# Sheet1.net
KiCad netlist of a schematic drawn in Altium Designer
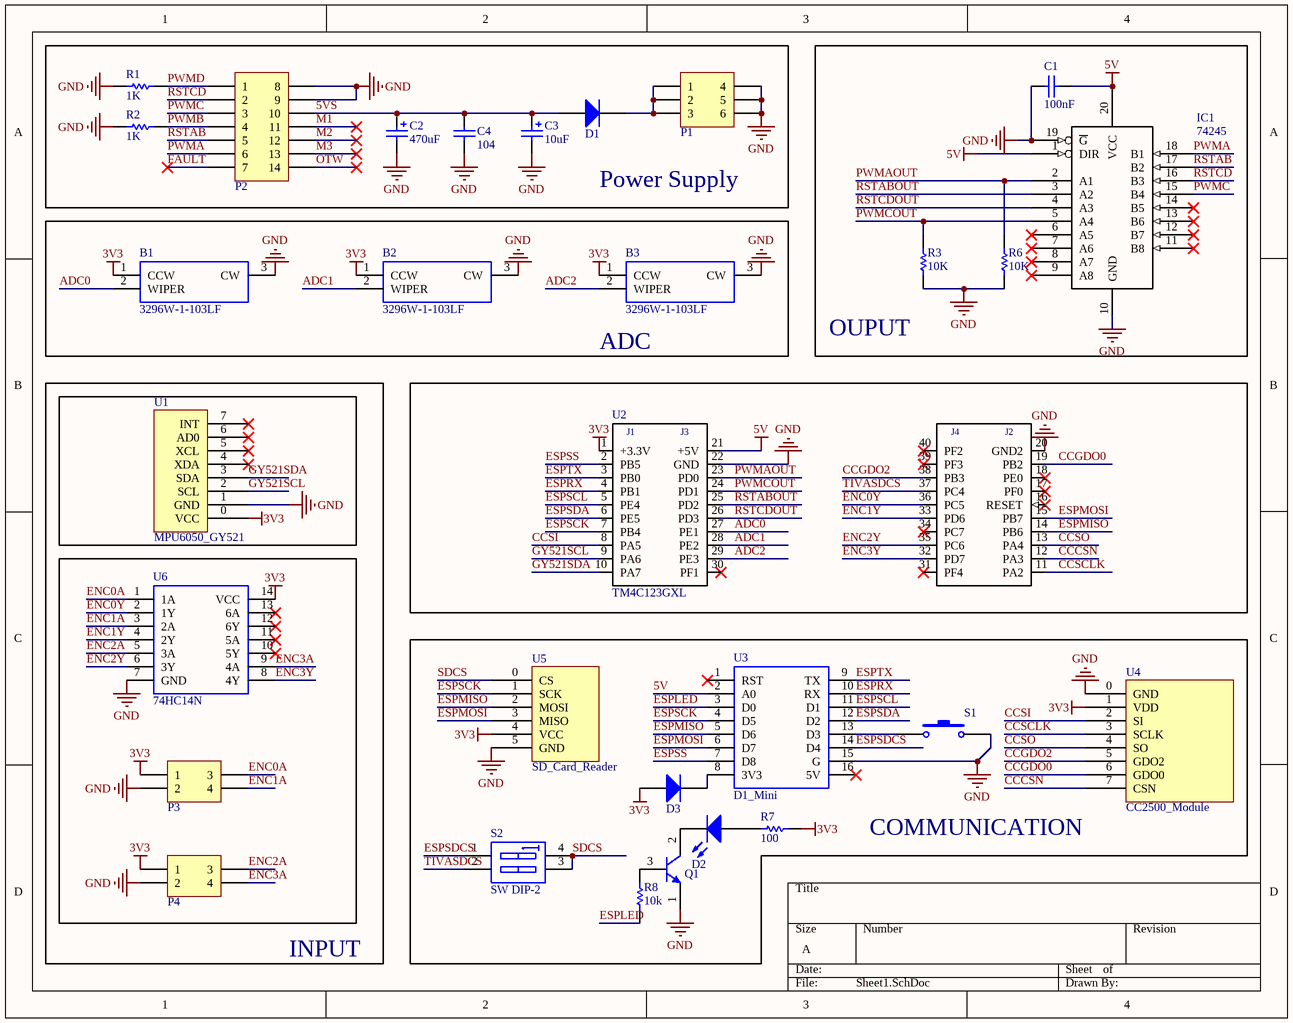
[diagram p0: Sheet1.SchDoc]

(export (version "E")
  (design (tool "Eeschema 10.0.6"))
  (components
    (comp (ref "B1")
      (value "3296W-1-103LF")
      (footprint "Rheostat")
      (fields (field (name "RS PART NUMBER") "5219647P"))
      (libsource (lib "AltiumLib") (part "Rheostat"))
    )
    (comp (ref "B2")
      (value "3296W-1-103LF")
      (footprint "Rheostat")
      (fields (field (name "RS PART NUMBER") "5219647P"))
      (libsource (lib "AltiumLib") (part "Rheostat"))
    )
    (comp (ref "B3")
      (value "3296W-1-103LF")
      (footprint "Rheostat")
      (fields (field (name "RS PART NUMBER") "5219647P"))
      (libsource (lib "AltiumLib") (part "Rheostat"))
    )
    (comp (ref "C1")
      (value "100nF")
      (footprint "CN1")
      (description "Capacitor")
      (fields (field (name "Comment") "Cap Non-Pol"))
      (libsource (lib "PIF_Library") (part "Cap Non-Pol"))
    )
    (comp (ref "C2")
      (value "470uF")
      (footprint "CP1/2")
      (description "Polarized Capacitor (Radial)")
      (fields (field (name "Comment") "Cap Pol"))
      (libsource (lib "PIF_Library") (part "Cap Pol"))
    )
    (comp (ref "C3")
      (value "10uF")
      (footprint "CP1/2")
      (description "Polarized Capacitor (Radial)")
      (fields (field (name "Comment") "Cap Pol"))
      (libsource (lib "PIF_Library") (part "Cap Pol"))
    )
    (comp (ref "C4")
      (value "104")
      (footprint "CN1")
      (description "Capacitor")
      (fields (field (name "Comment") "Cap Non-Pol"))
      (libsource (lib "PIF_Library") (part "Cap Non-Pol"))
    )
    (comp (ref "D1")
      (value "Diode")
      (footprint "D1A")
      (description "Default Diode")
      (libsource (lib "PIF_Library") (part "Diode"))
    )
    (comp (ref "D2") (value "LED") (footprint "LED-3mm") (libsource (lib "PIF_Library") (part "LED")))
    (comp (ref "D3")
      (value "Diode")
      (footprint "D1A")
      (description "Default Diode")
      (libsource (lib "PIF_Library") (part "Diode"))
    )
    (comp (ref "IC1")
      (value "74245")
      (footprint "DIP20")
      (description "Octal bus tranceiver; 3-state")
      (fields (field (name "COPYRIGHT BY") "VanDungEvn@gmail.com"))
      (libsource (lib "My Library") (part "74245_1"))
    )
    (comp (ref "P1")
      (value "Header 3X2")
      (footprint "JP3x2")
      (description "Header, 3-Pin, Dual row")
      (fields (field (name "PUBLISHER") "Altium Limited"))
      (libsource (lib "PIF_Library") (part "Header 3X2"))
    )
    (comp (ref "P2")
      (value "Header 7X2")
      (footprint "JP7X2")
      (description "Header, 7-Pin, Dual row")
      (fields (field (name "PUBLISHER") "Altium Limited"))
      (libsource (lib "PIF_Library") (part "Header 7X2"))
    )
    (comp (ref "P3")
      (value "Header 2X2")
      (footprint "JP2X2")
      (description "Header, 2-Pin, Dual row")
      (fields (field (name "PUBLISHER") "Altium Limited"))
      (libsource (lib "PIF_Library") (part "Header 2X2"))
    )
    (comp (ref "P4")
      (value "Header 2X2")
      (footprint "JP2X2")
      (description "Header, 2-Pin, Dual row")
      (fields (field (name "PUBLISHER") "Altium Limited"))
      (libsource (lib "PIF_Library") (part "Header 2X2"))
    )
    (comp (ref "Q1")
      (value "C1815")
      (footprint "QTO-92")
      (description "NPN Bipolar Transistor")
      (libsource (lib "PIF_Library") (part "C1815"))
    )
    (comp (ref "R1")
      (value "1K")
      (footprint "RES 1/2W")
      (description "Resistor")
      (fields (field (name "Comment") "RESISTOR"))
      (libsource (lib "PIF_Library") (part "RESISTOR"))
    )
    (comp (ref "R2")
      (value "1K")
      (footprint "RES 1/2W")
      (description "Resistor")
      (fields (field (name "Comment") "RESISTOR"))
      (libsource (lib "PIF_Library") (part "RESISTOR"))
    )
    (comp (ref "R3")
      (value "10K")
      (footprint "RES 1/2W")
      (description "Resistor")
      (fields (field (name "Comment") "RESISTOR"))
      (libsource (lib "PIF_Library") (part "RESISTOR"))
    )
    (comp (ref "R6")
      (value "10K")
      (footprint "RES 1/2W")
      (description "Resistor")
      (fields (field (name "Comment") "RESISTOR"))
      (libsource (lib "PIF_Library") (part "RESISTOR"))
    )
    (comp (ref "R7")
      (value "100")
      (footprint "RES 1/2W")
      (description "Resistor")
      (fields (field (name "Comment") "RESISTOR"))
      (libsource (lib "PIF_Library") (part "RESISTOR"))
    )
    (comp (ref "R8")
      (value "10k")
      (footprint "RES 1/2W")
      (description "Resistor")
      (fields (field (name "Comment") "RESISTOR"))
      (libsource (lib "PIF_Library") (part "RESISTOR"))
    )
    (comp (ref "S1")
      (value "Tact SW - 2Pin")
      (footprint "SW2")
      (description "Switch button 2 pin")
      (libsource (lib "PIF_Library") (part "Tact SW - 2Pin"))
    )
    (comp (ref "S2")
      (value "SW DIP-2")
      (footprint "DIPSWITCH2")
      (description "DIP Switch, 2 Position, SPST")
      (fields (field (name "PUBLISHER") "Altium Limited"))
      (libsource (lib "My Library") (part "SW DIP-2"))
    )
    (comp (ref "U1")
      (value "MPU6050_GY521")
      (footprint "MPU6050_GY521")
      (libsource (lib "AltiumLib") (part "MPU6050_GY521"))
    )
    (comp (ref "U2")
      (value "TM4C123GXL")
      (footprint "EK-TM4C123GXL")
      (libsource (lib "AltiumLib") (part "EK-TM4C123GXL"))
    )
    (comp (ref "U3") (value "D1_Mini") (footprint "D1_Mini") (libsource (lib "AltiumLib") (part "D1_Mini")))
    (comp (ref "U4")
      (value "CC2500_Module")
      (footprint "CC2500_module")
      (libsource (lib "AltiumLib") (part "CC2500_Module"))
    )
    (comp (ref "U5")
      (value "SD_Card_Reader")
      (footprint "SD_Card_Reader")
      (libsource (lib "AltiumLib") (part "SD_Card_Reader"))
    )
    (comp (ref "U6") (value "74HC14N") (footprint "74HC14N") (libsource (lib "AltiumLib") (part "74HC14N")))
  )
  (nets
    (net (code "1") (name "/5VS") (class "Default")
      (node (ref "C2") (pin "1") (pinfunction "1_1") (pintype "passive"))
      (node (ref "C3") (pin "1") (pinfunction "1_1") (pintype "passive"))
      (node (ref "C4") (pin "1") (pinfunction "1_1") (pintype "passive"))
      (node (ref "D1") (pin "1") (pinfunction "A_1") (pintype "passive"))
      (node (ref "P2") (pin "10") (pinfunction "10_10") (pintype "passive"))
    )
    (net (code "2") (name "/ADC0") (class "Default")
      (node (ref "B1") (pin "2") (pinfunction "WIPER_2") (pintype "passive"))
      (node (ref "U2") (pin "27") (pinfunction "PE1_27") (pintype "bidirectional"))
    )
    (net (code "3") (name "/ADC1") (class "Default")
      (node (ref "B2") (pin "2") (pinfunction "WIPER_2") (pintype "passive"))
      (node (ref "U2") (pin "28") (pinfunction "PE2_28") (pintype "bidirectional"))
    )
    (net (code "4") (name "/ADC2") (class "Default")
      (node (ref "B3") (pin "2") (pinfunction "WIPER_2") (pintype "passive"))
      (node (ref "U2") (pin "29") (pinfunction "PE3_29") (pintype "bidirectional"))
    )
    (net (code "5") (name "/CCCSN") (class "Default")
      (node (ref "U2") (pin "12") (pinfunction "PA3_12") (pintype "bidirectional"))
      (node (ref "U4") (pin "7") (pinfunction "CSN_7") (pintype "passive"))
    )
    (net (code "6") (name "/CCGDO0") (class "Default")
      (node (ref "U2") (pin "19") (pinfunction "PB2_19") (pintype "bidirectional"))
      (node (ref "U4") (pin "6") (pinfunction "GDO0_6") (pintype "passive"))
    )
    (net (code "7") (name "/CCGDO2") (class "Default")
      (node (ref "U2") (pin "38") (pinfunction "PB3_38") (pintype "bidirectional"))
      (node (ref "U4") (pin "5") (pinfunction "GDO2_5") (pintype "passive"))
    )
    (net (code "8") (name "/CCSCLK") (class "Default")
      (node (ref "U2") (pin "11") (pinfunction "PA2_11") (pintype "bidirectional"))
      (node (ref "U4") (pin "3") (pinfunction "SCLK_3") (pintype "passive"))
    )
    (net (code "9") (name "/CCSI") (class "Default")
      (node (ref "U2") (pin "8") (pinfunction "PA5_8") (pintype "bidirectional"))
      (node (ref "U4") (pin "2") (pinfunction "SI_2") (pintype "passive"))
    )
    (net (code "10") (name "/CCSO") (class "Default")
      (node (ref "U2") (pin "13") (pinfunction "PA4_13") (pintype "bidirectional"))
      (node (ref "U4") (pin "4") (pinfunction "SO_4") (pintype "passive"))
    )
    (net (code "11") (name "/ENC0A") (class "Default")
      (node (ref "P3") (pin "3") (pinfunction "3_3") (pintype "passive"))
      (node (ref "U6") (pin "1") (pinfunction "1A_1") (pintype "passive"))
    )
    (net (code "12") (name "/ENC0Y") (class "Default")
      (node (ref "U2") (pin "36") (pinfunction "PC5_36") (pintype "bidirectional"))
      (node (ref "U6") (pin "2") (pinfunction "1Y_2") (pintype "passive"))
    )
    (net (code "13") (name "/ENC1A") (class "Default")
      (node (ref "P3") (pin "4") (pinfunction "4_4") (pintype "passive"))
      (node (ref "U6") (pin "3") (pinfunction "2A_3") (pintype "passive"))
    )
    (net (code "14") (name "/ENC1Y") (class "Default")
      (node (ref "U2") (pin "33") (pinfunction "PD6_33") (pintype "bidirectional"))
      (node (ref "U6") (pin "4") (pinfunction "2Y_4") (pintype "passive"))
    )
    (net (code "15") (name "/ENC2A") (class "Default")
      (node (ref "P4") (pin "3") (pinfunction "3_3") (pintype "passive"))
      (node (ref "U6") (pin "5") (pinfunction "3A_5") (pintype "passive"))
    )
    (net (code "16") (name "/ENC2Y") (class "Default")
      (node (ref "U2") (pin "35") (pinfunction "PC6_35") (pintype "bidirectional"))
      (node (ref "U6") (pin "6") (pinfunction "3Y_6") (pintype "passive"))
    )
    (net (code "17") (name "/ENC3A") (class "Default")
      (node (ref "P4") (pin "4") (pinfunction "4_4") (pintype "passive"))
      (node (ref "U6") (pin "9") (pinfunction "4A_9") (pintype "passive"))
    )
    (net (code "18") (name "/ENC3Y") (class "Default")
      (node (ref "U2") (pin "32") (pinfunction "PD7_32") (pintype "bidirectional"))
      (node (ref "U6") (pin "8") (pinfunction "4Y_8") (pintype "passive"))
    )
    (net (code "19") (name "/ESPLED") (class "Default")
      (node (ref "R8") (pin "1") (pinfunction "1_1") (pintype "passive"))
      (node (ref "U3") (pin "3") (pinfunction "D0_3") (pintype "passive"))
    )
    (net (code "20") (name "/ESPMISO") (class "Default")
      (node (ref "U2") (pin "14") (pinfunction "PB6_14") (pintype "bidirectional"))
      (node (ref "U3") (pin "5") (pinfunction "D6_5") (pintype "passive"))
      (node (ref "U5") (pin "2") (pinfunction "MOSI_2") (pintype "passive"))
    )
    (net (code "21") (name "/ESPMOSI") (class "Default")
      (node (ref "U2") (pin "15") (pinfunction "PB7_15") (pintype "bidirectional"))
      (node (ref "U3") (pin "6") (pinfunction "D7_6") (pintype "passive"))
      (node (ref "U5") (pin "3") (pinfunction "MISO_3") (pintype "passive"))
    )
    (net (code "22") (name "/ESPRX") (class "Default")
      (node (ref "U2") (pin "4") (pinfunction "PB1_4") (pintype "bidirectional"))
      (node (ref "U3") (pin "10") (pinfunction "RX_10") (pintype "passive"))
    )
    (net (code "23") (name "/ESPSCK") (class "Default")
      (node (ref "U2") (pin "7") (pinfunction "PB4_7") (pintype "bidirectional"))
      (node (ref "U3") (pin "4") (pinfunction "D5_4") (pintype "passive"))
      (node (ref "U5") (pin "1") (pinfunction "SCK_1") (pintype "passive"))
    )
    (net (code "24") (name "/ESPSCL") (class "Default")
      (node (ref "U2") (pin "5") (pinfunction "PE4_5") (pintype "bidirectional"))
      (node (ref "U3") (pin "11") (pinfunction "D1_11") (pintype "passive"))
    )
    (net (code "25") (name "/ESPSDA") (class "Default")
      (node (ref "U2") (pin "6") (pinfunction "PE5_6") (pintype "bidirectional"))
      (node (ref "U3") (pin "12") (pinfunction "D2_12") (pintype "passive"))
    )
    (net (code "26") (name "/ESPSDCS") (class "Default")
      (node (ref "S2") (pin "1") (pinfunction "A1_1") (pintype "passive"))
      (node (ref "U3") (pin "14") (pinfunction "D4_14") (pintype "passive"))
    )
    (net (code "27") (name "/ESPSS") (class "Default")
      (node (ref "U2") (pin "2") (pinfunction "PB5_2") (pintype "bidirectional"))
      (node (ref "U3") (pin "7") (pinfunction "D8_7") (pintype "passive"))
    )
    (net (code "28") (name "/ESPTX") (class "Default")
      (node (ref "U2") (pin "3") (pinfunction "PB0_3") (pintype "bidirectional"))
      (node (ref "U3") (pin "9") (pinfunction "TX_9") (pintype "passive"))
    )
    (net (code "29") (name "/FAULT") (class "Default")
      (node (ref "P2") (pin "7") (pinfunction "7_7") (pintype "passive+no_connect"))
    )
    (net (code "30") (name "/GY521SCL") (class "Default")
      (node (ref "U1") (pin "2") (pinfunction "SCL_2") (pintype "passive"))
      (node (ref "U2") (pin "9") (pinfunction "PA6_9") (pintype "bidirectional"))
    )
    (net (code "31") (name "/GY521SDA") (class "Default")
      (node (ref "U1") (pin "3") (pinfunction "SDA_3") (pintype "passive"))
      (node (ref "U2") (pin "10") (pinfunction "PA7_10") (pintype "bidirectional"))
    )
    (net (code "32") (name "/M1") (class "Default")
      (node (ref "P2") (pin "11") (pinfunction "11_11") (pintype "passive+no_connect"))
    )
    (net (code "33") (name "/M2") (class "Default")
      (node (ref "P2") (pin "12") (pinfunction "12_12") (pintype "passive+no_connect"))
    )
    (net (code "34") (name "/M3") (class "Default")
      (node (ref "P2") (pin "13") (pinfunction "13_13") (pintype "passive+no_connect"))
    )
    (net (code "35") (name "/OTW") (class "Default")
      (node (ref "P2") (pin "14") (pinfunction "14_14") (pintype "passive+no_connect"))
    )
    (net (code "36") (name "/PWMA") (class "Default")
      (node (ref "IC1") (pin "18") (pinfunction "B1_18") (pintype "input"))
      (node (ref "P2") (pin "6") (pinfunction "6_6") (pintype "passive"))
    )
    (net (code "37") (name "/PWMAOUT") (class "Default")
      (node (ref "IC1") (pin "2") (pinfunction "A1_2") (pintype "tri_state"))
      (node (ref "R6") (pin "2") (pinfunction "2_2") (pintype "passive"))
      (node (ref "U2") (pin "23") (pinfunction "PD0_23") (pintype "bidirectional"))
    )
    (net (code "38") (name "/PWMB") (class "Default")
      (node (ref "P2") (pin "4") (pinfunction "4_4") (pintype "passive"))
      (node (ref "R2") (pin "2") (pinfunction "2_2") (pintype "passive"))
    )
    (net (code "39") (name "/PWMC") (class "Default")
      (node (ref "IC1") (pin "15") (pinfunction "B4_15") (pintype "input"))
      (node (ref "P2") (pin "3") (pinfunction "3_3") (pintype "passive"))
    )
    (net (code "40") (name "/PWMCOUT") (class "Default")
      (node (ref "IC1") (pin "5") (pinfunction "A4_5") (pintype "tri_state"))
      (node (ref "R3") (pin "2") (pinfunction "2_2") (pintype "passive"))
      (node (ref "U2") (pin "24") (pinfunction "PD1_24") (pintype "bidirectional"))
    )
    (net (code "41") (name "/PWMD") (class "Default")
      (node (ref "P2") (pin "1") (pinfunction "1_1") (pintype "passive"))
      (node (ref "R1") (pin "2") (pinfunction "2_2") (pintype "passive"))
    )
    (net (code "42") (name "/RSTAB") (class "Default")
      (node (ref "IC1") (pin "17") (pinfunction "B2_17") (pintype "input"))
      (node (ref "P2") (pin "5") (pinfunction "5_5") (pintype "passive"))
    )
    (net (code "43") (name "/RSTABOUT") (class "Default")
      (node (ref "IC1") (pin "3") (pinfunction "A2_3") (pintype "tri_state"))
      (node (ref "U2") (pin "25") (pinfunction "PD2_25") (pintype "bidirectional"))
    )
    (net (code "44") (name "/RSTCD") (class "Default")
      (node (ref "IC1") (pin "16") (pinfunction "B3_16") (pintype "input"))
      (node (ref "P2") (pin "2") (pinfunction "2_2") (pintype "passive"))
    )
    (net (code "45") (name "/RSTCDOUT") (class "Default")
      (node (ref "IC1") (pin "4") (pinfunction "A3_4") (pintype "tri_state"))
      (node (ref "U2") (pin "26") (pinfunction "PD3_26") (pintype "bidirectional"))
    )
    (net (code "46") (name "/SDCS") (class "Default")
      (node (ref "S2") (pin "3") (pinfunction "B2_3") (pintype "passive"))
      (node (ref "S2") (pin "4") (pinfunction "B1_4") (pintype "passive"))
      (node (ref "U5") (pin "0") (pinfunction "CS_0") (pintype "passive"))
    )
    (net (code "47") (name "/TIVASDCS") (class "Default")
      (node (ref "S2") (pin "2") (pinfunction "A2_2") (pintype "passive"))
      (node (ref "U2") (pin "37") (pinfunction "PC4_37") (pintype "bidirectional"))
    )
    (net (code "48") (name "3V3") (class "Default")
      (node (ref "B1") (pin "1") (pinfunction "CCW_1") (pintype "passive"))
      (node (ref "B2") (pin "1") (pinfunction "CCW_1") (pintype "passive"))
      (node (ref "B3") (pin "1") (pinfunction "CCW_1") (pintype "passive"))
      (node (ref "D3") (pin "1") (pinfunction "A_1") (pintype "passive"))
      (node (ref "P3") (pin "1") (pinfunction "1_1") (pintype "passive"))
      (node (ref "P4") (pin "1") (pinfunction "1_1") (pintype "passive"))
      (node (ref "R7") (pin "2") (pinfunction "2_2") (pintype "passive"))
      (node (ref "U1") (pin "0") (pinfunction "VCC_0") (pintype "power_in"))
      (node (ref "U2") (pin "1") (pinfunction "+3.3V_1") (pintype "power_in"))
      (node (ref "U4") (pin "1") (pinfunction "VDD_1") (pintype "passive"))
      (node (ref "U5") (pin "4") (pinfunction "VCC_4") (pintype "power_in"))
      (node (ref "U6") (pin "14") (pinfunction "VCC_14") (pintype "passive"))
    )
    (net (code "49") (name "5V") (class "Default")
      (node (ref "C1") (pin "2") (pinfunction "2_2") (pintype "passive"))
      (node (ref "IC1") (pin "1") (pinfunction "DIR_1") (pintype "input"))
      (node (ref "IC1") (pin "20") (pinfunction "VCC_20") (pintype "power_in"))
      (node (ref "U2") (pin "21") (pinfunction "+5V_21") (pintype "power_in"))
      (node (ref "U3") (pin "2") (pinfunction "A0_2") (pintype "passive"))
    )
    (net (code "50") (name "GND") (class "Default")
      (node (ref "B1") (pin "3") (pinfunction "CW_3") (pintype "passive"))
      (node (ref "B2") (pin "3") (pinfunction "CW_3") (pintype "passive"))
      (node (ref "B3") (pin "3") (pinfunction "CW_3") (pintype "passive"))
      (node (ref "C1") (pin "1") (pinfunction "1_1") (pintype "passive"))
      (node (ref "C2") (pin "2") (pinfunction "2_2") (pintype "passive"))
      (node (ref "C3") (pin "2") (pinfunction "2_2") (pintype "passive"))
      (node (ref "C4") (pin "2") (pinfunction "2_2") (pintype "passive"))
      (node (ref "IC1") (pin "10") (pinfunction "GND_10") (pintype "power_in"))
      (node (ref "IC1") (pin "19") (pinfunction "~{G}_19") (pintype "input"))
      (node (ref "P1") (pin "4") (pinfunction "4_4") (pintype "passive"))
      (node (ref "P1") (pin "5") (pinfunction "5_5") (pintype "passive"))
      (node (ref "P1") (pin "6") (pinfunction "6_6") (pintype "passive"))
      (node (ref "P2") (pin "8") (pinfunction "8_8") (pintype "passive"))
      (node (ref "P2") (pin "9") (pinfunction "9_9") (pintype "passive"))
      (node (ref "P3") (pin "2") (pinfunction "2_2") (pintype "passive"))
      (node (ref "P4") (pin "2") (pinfunction "2_2") (pintype "passive"))
      (node (ref "Q1") (pin "1") (pinfunction "E_1") (pintype "passive"))
      (node (ref "R1") (pin "1") (pinfunction "1_1") (pintype "passive"))
      (node (ref "R2") (pin "1") (pinfunction "1_1") (pintype "passive"))
      (node (ref "R3") (pin "1") (pinfunction "1_1") (pintype "passive"))
      (node (ref "R6") (pin "1") (pinfunction "1_1") (pintype "passive"))
      (node (ref "S1") (pin "2") (pinfunction "2_2") (pintype "passive"))
      (node (ref "U1") (pin "1") (pinfunction "GND_1") (pintype "power_in"))
      (node (ref "U2") (pin "20") (pinfunction "GND2_20") (pintype "power_in"))
      (node (ref "U2") (pin "22") (pinfunction "GND_22") (pintype "power_in"))
      (node (ref "U3") (pin "15") (pinfunction "G_15") (pintype "passive"))
      (node (ref "U4") (pin "0") (pinfunction "GND_0") (pintype "power_in"))
      (node (ref "U5") (pin "5") (pinfunction "GND_5") (pintype "power_in"))
      (node (ref "U6") (pin "7") (pinfunction "GND_7") (pintype "passive"))
    )
    (net (code "51") (name "Net-(D1-K)") (class "Default")
      (node (ref "D1") (pin "2") (pinfunction "K_2") (pintype "passive"))
      (node (ref "P1") (pin "1") (pinfunction "1_1") (pintype "passive"))
      (node (ref "P1") (pin "2") (pinfunction "2_2") (pintype "passive"))
      (node (ref "P1") (pin "3") (pinfunction "3_3") (pintype "passive"))
    )
    (net (code "52") (name "Net-(D2-A)") (class "Default")
      (node (ref "D2") (pin "1") (pinfunction "A_1") (pintype "passive"))
      (node (ref "R7") (pin "1") (pinfunction "1_1") (pintype "passive"))
    )
    (net (code "53") (name "Net-(D2-K)") (class "Default")
      (node (ref "D2") (pin "2") (pinfunction "K_2") (pintype "passive"))
      (node (ref "Q1") (pin "2") (pinfunction "C_2") (pintype "passive"))
    )
    (net (code "54") (name "Net-(D3-K)") (class "Default")
      (node (ref "D3") (pin "2") (pinfunction "K_2") (pintype "passive"))
      (node (ref "U3") (pin "8") (pinfunction "3V3_8") (pintype "passive"))
    )
    (net (code "55") (name "Net-(Q1-B)") (class "Default")
      (node (ref "Q1") (pin "3") (pinfunction "B_3") (pintype "passive"))
      (node (ref "R8") (pin "2") (pinfunction "2_2") (pintype "passive"))
    )
    (net (code "56") (name "Net-(U3-D3)") (class "Default")
      (node (ref "S1") (pin "1") (pinfunction "1_1") (pintype "passive"))
      (node (ref "U3") (pin "13") (pinfunction "D3_13") (pintype "passive"))
    )
    (net (code "57") (name "unconnected-(IC1-A5-Pad6)") (class "Default")
      (node (ref "IC1") (pin "6") (pinfunction "A5_6") (pintype "tri_state+no_connect"))
    )
    (net (code "58") (name "unconnected-(IC1-A6-Pad7)") (class "Default")
      (node (ref "IC1") (pin "7") (pinfunction "A6_7") (pintype "tri_state+no_connect"))
    )
    (net (code "59") (name "unconnected-(IC1-A7-Pad8)") (class "Default")
      (node (ref "IC1") (pin "8") (pinfunction "A7_8") (pintype "tri_state+no_connect"))
    )
    (net (code "60") (name "unconnected-(IC1-A8-Pad9)") (class "Default")
      (node (ref "IC1") (pin "9") (pinfunction "A8_9") (pintype "tri_state+no_connect"))
    )
    (net (code "61") (name "unconnected-(IC1-B5-Pad14)") (class "Default")
      (node (ref "IC1") (pin "14") (pinfunction "B5_14") (pintype "input+no_connect"))
    )
    (net (code "62") (name "unconnected-(IC1-B6-Pad13)") (class "Default")
      (node (ref "IC1") (pin "13") (pinfunction "B6_13") (pintype "input+no_connect"))
    )
    (net (code "63") (name "unconnected-(IC1-B7-Pad12)") (class "Default")
      (node (ref "IC1") (pin "12") (pinfunction "B7_12") (pintype "input+no_connect"))
    )
    (net (code "64") (name "unconnected-(IC1-B8-Pad11)") (class "Default")
      (node (ref "IC1") (pin "11") (pinfunction "B8_11") (pintype "input+no_connect"))
    )
    (net (code "65") (name "unconnected-(U1-AD0-Pad6)") (class "Default")
      (node (ref "U1") (pin "6") (pinfunction "AD0_6") (pintype "passive+no_connect"))
    )
    (net (code "66") (name "unconnected-(U1-INT-Pad7)") (class "Default")
      (node (ref "U1") (pin "7") (pinfunction "INT_7") (pintype "passive+no_connect"))
    )
    (net (code "67") (name "unconnected-(U1-XCL-Pad5)") (class "Default")
      (node (ref "U1") (pin "5") (pinfunction "XCL_5") (pintype "passive+no_connect"))
    )
    (net (code "68") (name "unconnected-(U1-XDA-Pad4)") (class "Default")
      (node (ref "U1") (pin "4") (pinfunction "XDA_4") (pintype "passive+no_connect"))
    )
    (net (code "69") (name "unconnected-(U2-PC7-Pad34)") (class "Default")
      (node (ref "U2") (pin "34") (pinfunction "PC7_34") (pintype "bidirectional+no_connect"))
    )
    (net (code "70") (name "unconnected-(U2-PE0-Pad18)") (class "Default")
      (node (ref "U2") (pin "18") (pinfunction "PE0_18") (pintype "bidirectional+no_connect"))
    )
    (net (code "71") (name "unconnected-(U2-PF0-Pad17)") (class "Default")
      (node (ref "U2") (pin "17") (pinfunction "PF0_17") (pintype "bidirectional+no_connect"))
    )
    (net (code "72") (name "unconnected-(U2-PF1-Pad30)") (class "Default")
      (node (ref "U2") (pin "30") (pinfunction "PF1_30") (pintype "bidirectional+no_connect"))
    )
    (net (code "73") (name "unconnected-(U2-PF2-Pad40)") (class "Default")
      (node (ref "U2") (pin "40") (pinfunction "PF2_40") (pintype "bidirectional+no_connect"))
    )
    (net (code "74") (name "unconnected-(U2-PF3-Pad39)") (class "Default")
      (node (ref "U2") (pin "39") (pinfunction "PF3_39") (pintype "bidirectional+no_connect"))
    )
    (net (code "75") (name "unconnected-(U2-PF4-Pad31)") (class "Default")
      (node (ref "U2") (pin "31") (pinfunction "PF4_31") (pintype "bidirectional+no_connect"))
    )
    (net (code "76") (name "unconnected-(U2-RESET-Pad16)") (class "Default")
      (node (ref "U2") (pin "16") (pinfunction "RESET_16") (pintype "input+no_connect"))
    )
    (net (code "77") (name "unconnected-(U3-5V-Pad16)") (class "Default")
      (node (ref "U3") (pin "16") (pinfunction "5V_16") (pintype "passive+no_connect"))
    )
    (net (code "78") (name "unconnected-(U3-RST-Pad1)") (class "Default")
      (node (ref "U3") (pin "1") (pinfunction "RST_1") (pintype "passive+no_connect"))
    )
    (net (code "79") (name "unconnected-(U6-5A-Pad11)") (class "Default")
      (node (ref "U6") (pin "11") (pinfunction "5A_11") (pintype "passive+no_connect"))
    )
    (net (code "80") (name "unconnected-(U6-5Y-Pad10)") (class "Default")
      (node (ref "U6") (pin "10") (pinfunction "5Y_10") (pintype "passive+no_connect"))
    )
    (net (code "81") (name "unconnected-(U6-6A-Pad13)") (class "Default")
      (node (ref "U6") (pin "13") (pinfunction "6A_13") (pintype "passive+no_connect"))
    )
    (net (code "82") (name "unconnected-(U6-6Y-Pad12)") (class "Default")
      (node (ref "U6") (pin "12") (pinfunction "6Y_12") (pintype "passive+no_connect"))
    )
  )
)
